# 411_REV0.net
KiCad netlist of a schematic drawn in EAGLE
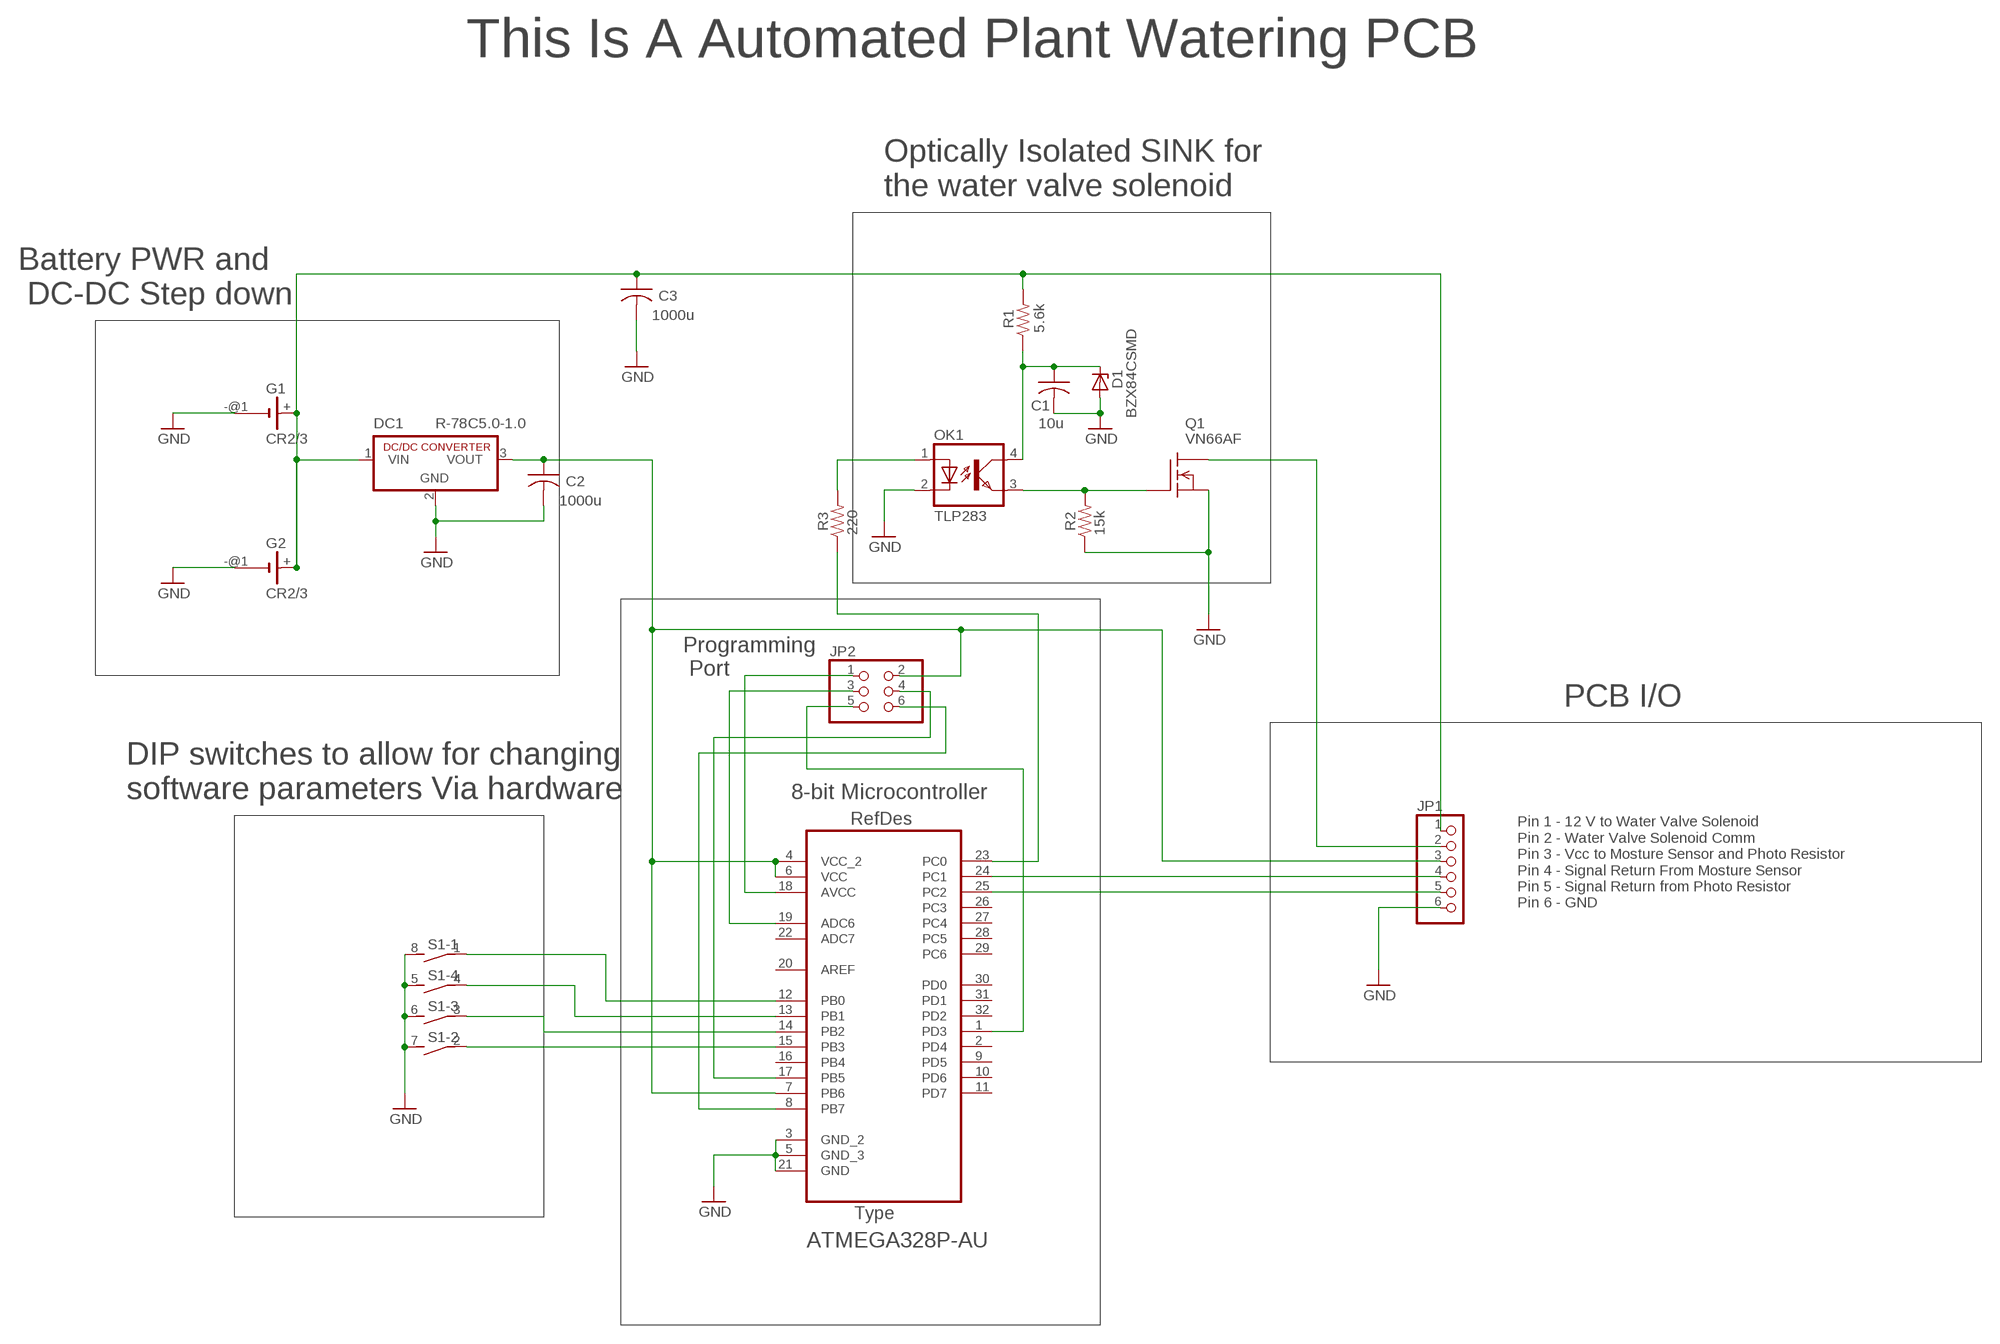
[diagram p0: schematic, sheet 1]

(export (version "E")
  (design (tool "Eeschema 10.0.6"))
  (components
    (comp (ref "ATMEGA328")
      (value "ATMEGA328P-AU")
      (footprint "eagle-import:QFP80P900X900X120-32N")
      (description "8-bit Microcontroller")
      (fields (field (name "MPN") "ATMEGA328P-AU"))
      (libsource (lib "eagle-import") (part "ATMEGA328P-AU"))
    )
    (comp (ref "C1")
      (value "C-USC0805")
      (footprint "eagle-import:C0805")
      (fields (field (name "C") "10u"))
      (libsource (lib "eagle-import") (part "C-USC0805"))
    )
    (comp (ref "C2")
      (value "C-USC0805")
      (footprint "eagle-import:C0805")
      (fields (field (name "C") "1000u"))
      (libsource (lib "eagle-import") (part "C-USC0805"))
    )
    (comp (ref "C3")
      (value "C-USC0805")
      (footprint "eagle-import:C0805")
      (fields (field (name "C") "1000u"))
      (libsource (lib "eagle-import") (part "C-USC0805"))
    )
    (comp (ref "D1")
      (value "BZX84CSMD")
      (footprint "eagle-import:TO236")
      (libsource (lib "eagle-import") (part "BZX84CSMD"))
    )
    (comp (ref "DC1")
      (value "R-78C5.0-1.0")
      (footprint "eagle-import:SIP3")
      (libsource (lib "eagle-import") (part "R-78C-1.05.0"))
    )
    (comp (ref "G1")
      (value "CR2/3")
      (footprint "eagle-import:CR2_3")
      (libsource (lib "eagle-import") (part "CR2/3"))
    )
    (comp (ref "G2")
      (value "CR2/3")
      (footprint "eagle-import:CR2_3")
      (libsource (lib "eagle-import") (part "CR2/3"))
    )
    (comp (ref "JP1")
      (value "PINHD-1X6")
      (footprint "eagle-import:1X06")
      (libsource (lib "eagle-import") (part "PINHD-1X6"))
    )
    (comp (ref "JP2")
      (value "PINHD-2X3")
      (footprint "eagle-import:2X03")
      (libsource (lib "eagle-import") (part "PINHD-2X3"))
    )
    (comp (ref "OK1")
      (value "TLP283")
      (footprint "eagle-import:MINI-FLAT-4")
      (libsource (lib "eagle-import") (part "TLP283"))
    )
    (comp (ref "Q1")
      (value "VN66AF")
      (footprint "eagle-import:TO202")
      (libsource (lib "eagle-import") (part "VN66AF"))
    )
    (comp (ref "R1")
      (value "R-US_M0805")
      (footprint "eagle-import:M0805")
      (fields (field (name "R") "5.6k"))
      (libsource (lib "eagle-import") (part "R-US_M0805"))
    )
    (comp (ref "R2")
      (value "R-US_M0805")
      (footprint "eagle-import:M0805")
      (fields (field (name "R") "15k"))
      (libsource (lib "eagle-import") (part "R-US_M0805"))
    )
    (comp (ref "R3")
      (value "R-US_M0805")
      (footprint "eagle-import:M0805")
      (fields (field (name "R") "220"))
      (libsource (lib "eagle-import") (part "R-US_M0805"))
    )
    (comp (ref "S1")
      (value "DIP04S")
      (footprint "eagle-import:DIP04S")
      (libsource (lib "eagle-import") (part "DIP04S"))
    )
  )
  (nets
    (net (code "1") (name "GND") (class "Default")
      (node (ref "ATMEGA328") (pin "21") (pinfunction "GND_21") (pintype "passive"))
      (node (ref "ATMEGA328") (pin "3") (pinfunction "GND_2_3") (pintype "passive"))
      (node (ref "ATMEGA328") (pin "5") (pinfunction "GND_3_5") (pintype "passive"))
      (node (ref "C1") (pin "2") (pinfunction "2_2") (pintype "passive"))
      (node (ref "C2") (pin "2") (pinfunction "2_2") (pintype "passive"))
      (node (ref "C3") (pin "2") (pinfunction "2_2") (pintype "passive"))
      (node (ref "D1") (pin "A") (pinfunction "A_A") (pintype "passive"))
      (node (ref "DC1") (pin "2") (pinfunction "GND_2") (pintype "passive"))
      (node (ref "G1") (pin "-@1") (pinfunction "-_-@1") (pintype "passive"))
      (node (ref "G2") (pin "-@1") (pinfunction "-_-@1") (pintype "passive"))
      (node (ref "JP1") (pin "6") (pinfunction "6_6") (pintype "passive"))
      (node (ref "OK1") (pin "2") (pinfunction "C_2") (pintype "passive"))
      (node (ref "Q1") (pin "1") (pinfunction "S_1") (pintype "passive"))
      (node (ref "R2") (pin "1") (pinfunction "1_1") (pintype "passive"))
      (node (ref "S1") (pin "5") (pinfunction "2_5") (pintype "passive"))
      (node (ref "S1") (pin "6") (pinfunction "2_6") (pintype "passive"))
      (node (ref "S1") (pin "7") (pinfunction "2_7") (pintype "passive"))
      (node (ref "S1") (pin "8") (pinfunction "2_8") (pintype "passive"))
    )
    (net (code "2") (name "Net-(ATMEGA328-ADC6)") (class "Default")
      (node (ref "ATMEGA328") (pin "19") (pinfunction "ADC6_19") (pintype "input"))
      (node (ref "JP2") (pin "3") (pinfunction "3_3") (pintype "passive"))
    )
    (net (code "3") (name "Net-(ATMEGA328-AVCC)") (class "Default")
      (node (ref "ATMEGA328") (pin "18") (pinfunction "AVCC_18") (pintype "power_in"))
      (node (ref "JP2") (pin "1") (pinfunction "1_1") (pintype "passive"))
    )
    (net (code "4") (name "Net-(ATMEGA328-PB0)") (class "Default")
      (node (ref "ATMEGA328") (pin "12") (pinfunction "PB0_12") (pintype "bidirectional"))
      (node (ref "S1") (pin "1") (pinfunction "1_1") (pintype "passive"))
    )
    (net (code "5") (name "Net-(ATMEGA328-PB1)") (class "Default")
      (node (ref "ATMEGA328") (pin "13") (pinfunction "PB1_13") (pintype "bidirectional"))
      (node (ref "S1") (pin "4") (pinfunction "1_4") (pintype "passive"))
    )
    (net (code "6") (name "Net-(ATMEGA328-PB2)") (class "Default")
      (node (ref "ATMEGA328") (pin "14") (pinfunction "PB2_14") (pintype "bidirectional"))
      (node (ref "S1") (pin "3") (pinfunction "1_3") (pintype "passive"))
    )
    (net (code "7") (name "Net-(ATMEGA328-PB3)") (class "Default")
      (node (ref "ATMEGA328") (pin "15") (pinfunction "PB3_15") (pintype "bidirectional"))
      (node (ref "S1") (pin "2") (pinfunction "1_2") (pintype "passive"))
    )
    (net (code "8") (name "Net-(ATMEGA328-PB5)") (class "Default")
      (node (ref "ATMEGA328") (pin "17") (pinfunction "PB5_17") (pintype "bidirectional"))
      (node (ref "JP2") (pin "4") (pinfunction "4_4") (pintype "passive"))
    )
    (net (code "9") (name "Net-(ATMEGA328-PB6)") (class "Default")
      (node (ref "ATMEGA328") (pin "4") (pinfunction "VCC_2_4") (pintype "power_in"))
      (node (ref "ATMEGA328") (pin "6") (pinfunction "VCC_6") (pintype "power_in"))
      (node (ref "ATMEGA328") (pin "7") (pinfunction "PB6_7") (pintype "bidirectional"))
      (node (ref "C2") (pin "1") (pinfunction "1_1") (pintype "passive"))
      (node (ref "DC1") (pin "3") (pinfunction "VOUT_3") (pintype "passive"))
      (node (ref "JP1") (pin "3") (pinfunction "3_3") (pintype "passive"))
      (node (ref "JP2") (pin "2") (pinfunction "2_2") (pintype "passive"))
    )
    (net (code "10") (name "Net-(ATMEGA328-PB7)") (class "Default")
      (node (ref "ATMEGA328") (pin "8") (pinfunction "PB7_8") (pintype "bidirectional"))
      (node (ref "JP2") (pin "6") (pinfunction "6_6") (pintype "passive"))
    )
    (net (code "11") (name "Net-(ATMEGA328-PC0)") (class "Default")
      (node (ref "ATMEGA328") (pin "23") (pinfunction "PC0_23") (pintype "bidirectional"))
      (node (ref "R3") (pin "1") (pinfunction "1_1") (pintype "passive"))
    )
    (net (code "12") (name "Net-(ATMEGA328-PC1)") (class "Default")
      (node (ref "ATMEGA328") (pin "24") (pinfunction "PC1_24") (pintype "bidirectional"))
      (node (ref "JP1") (pin "4") (pinfunction "4_4") (pintype "passive"))
    )
    (net (code "13") (name "Net-(ATMEGA328-PC2)") (class "Default")
      (node (ref "ATMEGA328") (pin "25") (pinfunction "PC2_25") (pintype "bidirectional"))
      (node (ref "JP1") (pin "5") (pinfunction "5_5") (pintype "passive"))
    )
    (net (code "14") (name "Net-(ATMEGA328-PD3)") (class "Default")
      (node (ref "ATMEGA328") (pin "1") (pinfunction "PD3_1") (pintype "bidirectional"))
      (node (ref "JP2") (pin "5") (pinfunction "5_5") (pintype "passive"))
    )
    (net (code "15") (name "Net-(DC1-VIN)") (class "Default")
      (node (ref "C3") (pin "1") (pinfunction "1_1") (pintype "passive"))
      (node (ref "DC1") (pin "1") (pinfunction "VIN_1") (pintype "passive"))
      (node (ref "G1") (pin "+") (pinfunction "+_+") (pintype "passive"))
      (node (ref "G2") (pin "+") (pinfunction "+_+") (pintype "passive"))
      (node (ref "JP1") (pin "1") (pinfunction "1_1") (pintype "passive"))
      (node (ref "R1") (pin "2") (pinfunction "2_2") (pintype "passive"))
    )
    (net (code "16") (name "Net-(OK1-A)") (class "Default")
      (node (ref "OK1") (pin "1") (pinfunction "A_1") (pintype "passive"))
      (node (ref "R3") (pin "2") (pinfunction "2_2") (pintype "passive"))
    )
    (net (code "17") (name "Net-(OK1-COL)") (class "Default")
      (node (ref "C1") (pin "1") (pinfunction "1_1") (pintype "passive"))
      (node (ref "D1") (pin "C") (pinfunction "C_C") (pintype "passive"))
      (node (ref "OK1") (pin "4") (pinfunction "COL_4") (pintype "passive"))
      (node (ref "R1") (pin "1") (pinfunction "1_1") (pintype "passive"))
    )
    (net (code "18") (name "Net-(OK1-EMIT)") (class "Default")
      (node (ref "OK1") (pin "3") (pinfunction "EMIT_3") (pintype "passive"))
      (node (ref "Q1") (pin "2") (pinfunction "G_2") (pintype "passive"))
      (node (ref "R2") (pin "2") (pinfunction "2_2") (pintype "passive"))
    )
    (net (code "19") (name "Net-(Q1-D)") (class "Default")
      (node (ref "JP1") (pin "2") (pinfunction "2_2") (pintype "passive"))
      (node (ref "Q1") (pin "3") (pinfunction "D_3") (pintype "passive"))
    )
    (net (code "20") (name "unconnected-(ATMEGA328-ADC7-Pad22)") (class "Default")
      (node (ref "ATMEGA328") (pin "22") (pinfunction "ADC7_22") (pintype "input"))
    )
    (net (code "21") (name "unconnected-(ATMEGA328-AREF-Pad20)") (class "Default")
      (node (ref "ATMEGA328") (pin "20") (pinfunction "AREF_20") (pintype "input"))
    )
    (net (code "22") (name "unconnected-(ATMEGA328-PB4-Pad16)") (class "Default")
      (node (ref "ATMEGA328") (pin "16") (pinfunction "PB4_16") (pintype "bidirectional"))
    )
    (net (code "23") (name "unconnected-(ATMEGA328-PC3-Pad26)") (class "Default")
      (node (ref "ATMEGA328") (pin "26") (pinfunction "PC3_26") (pintype "bidirectional"))
    )
    (net (code "24") (name "unconnected-(ATMEGA328-PC4-Pad27)") (class "Default")
      (node (ref "ATMEGA328") (pin "27") (pinfunction "PC4_27") (pintype "bidirectional"))
    )
    (net (code "25") (name "unconnected-(ATMEGA328-PC5-Pad28)") (class "Default")
      (node (ref "ATMEGA328") (pin "28") (pinfunction "PC5_28") (pintype "bidirectional"))
    )
    (net (code "26") (name "unconnected-(ATMEGA328-PC6-Pad29)") (class "Default")
      (node (ref "ATMEGA328") (pin "29") (pinfunction "PC6_29") (pintype "bidirectional"))
    )
    (net (code "27") (name "unconnected-(ATMEGA328-PD0-Pad30)") (class "Default")
      (node (ref "ATMEGA328") (pin "30") (pinfunction "PD0_30") (pintype "bidirectional"))
    )
    (net (code "28") (name "unconnected-(ATMEGA328-PD1-Pad31)") (class "Default")
      (node (ref "ATMEGA328") (pin "31") (pinfunction "PD1_31") (pintype "bidirectional"))
    )
    (net (code "29") (name "unconnected-(ATMEGA328-PD2-Pad32)") (class "Default")
      (node (ref "ATMEGA328") (pin "32") (pinfunction "PD2_32") (pintype "bidirectional"))
    )
    (net (code "30") (name "unconnected-(ATMEGA328-PD4-Pad2)") (class "Default")
      (node (ref "ATMEGA328") (pin "2") (pinfunction "PD4_2") (pintype "bidirectional"))
    )
    (net (code "31") (name "unconnected-(ATMEGA328-PD5-Pad9)") (class "Default")
      (node (ref "ATMEGA328") (pin "9") (pinfunction "PD5_9") (pintype "bidirectional"))
    )
    (net (code "32") (name "unconnected-(ATMEGA328-PD6-Pad10)") (class "Default")
      (node (ref "ATMEGA328") (pin "10") (pinfunction "PD6_10") (pintype "bidirectional"))
    )
    (net (code "33") (name "unconnected-(ATMEGA328-PD7-Pad11)") (class "Default")
      (node (ref "ATMEGA328") (pin "11") (pinfunction "PD7_11") (pintype "bidirectional"))
    )
    (net (code "34") (name "unconnected-(G1---Pad-@2)") (class "Default")
      (node (ref "G1") (pin "-@2") (pinfunction "-_-@2") (pintype "passive"))
    )
    (net (code "35") (name "unconnected-(G2---Pad-@2)") (class "Default")
      (node (ref "G2") (pin "-@2") (pinfunction "-_-@2") (pintype "passive"))
    )
  )
)
